# cutoff.net
KiCad netlist of a schematic drawn in EAGLE
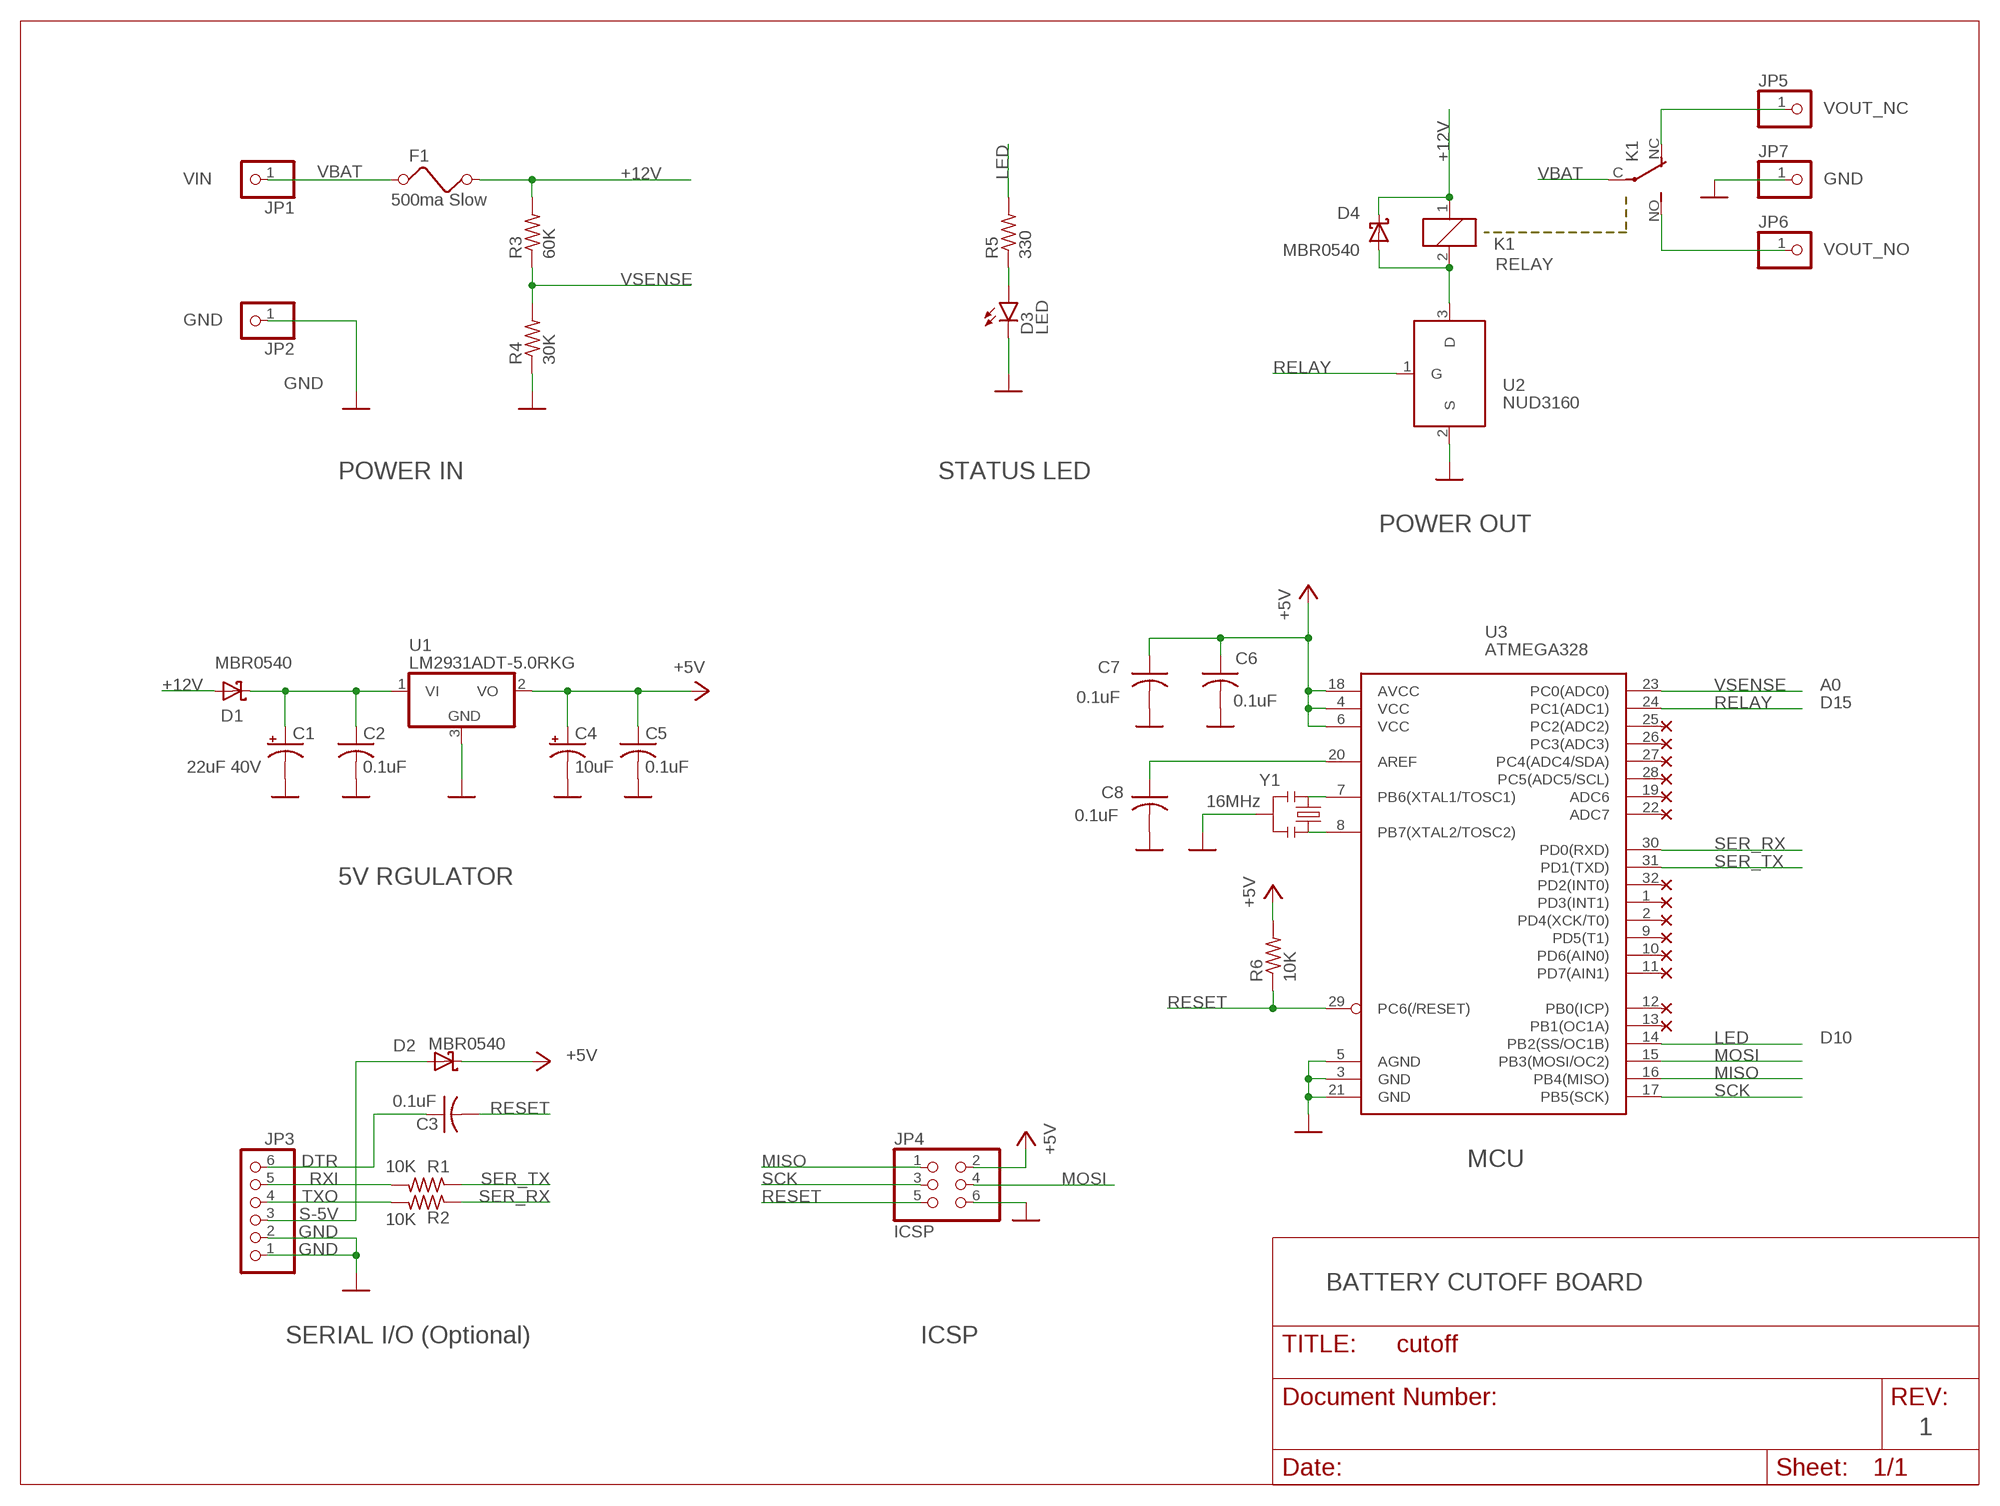
[diagram p0: schematic, sheet 1]

(export (version "E")
  (design (tool "Eeschema 10.0.6"))
  (components
    (comp (ref "C1")
      (value "22uF 40V")
      (footprint "eagle-import:UD-6,3X5,8_NICHICON")
      (libsource (lib "eagle-import") (part "CPOL-USUD-6,3X5,8"))
    )
    (comp (ref "C2")
      (value "0.1uF")
      (footprint "eagle-import:C0603K")
      (libsource (lib "eagle-import") (part "C-USC0603K"))
    )
    (comp (ref "C3")
      (value "0.1uF")
      (footprint "eagle-import:C0603K")
      (libsource (lib "eagle-import") (part "C-USC0603K"))
    )
    (comp (ref "C4")
      (value "10uF")
      (footprint "eagle-import:A_3216-18R")
      (libsource (lib "eagle-import") (part "CPOL-USA/3216-18R"))
    )
    (comp (ref "C5")
      (value "0.1uF")
      (footprint "eagle-import:C0603K")
      (libsource (lib "eagle-import") (part "C-USC0603K"))
    )
    (comp (ref "C6")
      (value "0.1uF")
      (footprint "eagle-import:C0603K")
      (libsource (lib "eagle-import") (part "C-USC0603K"))
    )
    (comp (ref "C7")
      (value "0.1uF")
      (footprint "eagle-import:C0603K")
      (libsource (lib "eagle-import") (part "C-USC0603K"))
    )
    (comp (ref "C8")
      (value "0.1uF")
      (footprint "eagle-import:C0603K")
      (libsource (lib "eagle-import") (part "C-USC0603K"))
    )
    (comp (ref "D1")
      (value "MBR0540")
      (footprint "eagle-import:SOD123FL")
      (libsource (lib "eagle-import") (part "SMF5.0AT1"))
    )
    (comp (ref "D2")
      (value "MBR0540")
      (footprint "eagle-import:SOD123FL")
      (libsource (lib "eagle-import") (part "SMF5.0AT1"))
    )
    (comp (ref "D3")
      (value "LED")
      (footprint "eagle-import:LED")
      (libsource (lib "eagle-import") (part "LED"))
    )
    (comp (ref "D4")
      (value "MBR0540")
      (footprint "eagle-import:SOD123FL")
      (libsource (lib "eagle-import") (part "SMF5.0AT1"))
    )
    (comp (ref "F1")
      (value "500ma Slow")
      (footprint "eagle-import:1206")
      (libsource (lib "eagle-import") (part "FUSE"))
    )
    (comp (ref "JP1")
      (value "WIRE_PAD")
      (footprint "eagle-import:WIRE_PAD")
      (libsource (lib "eagle-import") (part "WIRE_PAD"))
    )
    (comp (ref "JP2")
      (value "WIRE_PAD")
      (footprint "eagle-import:WIRE_PAD")
      (libsource (lib "eagle-import") (part "WIRE_PAD"))
    )
    (comp (ref "JP3")
      (value "PINHD-1X6")
      (footprint "eagle-import:1X06")
      (libsource (lib "eagle-import") (part "PINHD-1X6"))
    )
    (comp (ref "JP4")
      (value "ICSP")
      (footprint "eagle-import:2X03")
      (libsource (lib "eagle-import") (part "PINHD-2X3"))
    )
    (comp (ref "JP5")
      (value "WIRE_PAD")
      (footprint "eagle-import:WIRE_PAD")
      (libsource (lib "eagle-import") (part "WIRE_PAD"))
    )
    (comp (ref "JP6")
      (value "WIRE_PAD")
      (footprint "eagle-import:WIRE_PAD")
      (libsource (lib "eagle-import") (part "WIRE_PAD"))
    )
    (comp (ref "JP7")
      (value "WIRE_PAD")
      (footprint "eagle-import:WIRE_PAD")
      (libsource (lib "eagle-import") (part "WIRE_PAD"))
    )
    (comp (ref "K1")
      (value "RELAY")
      (footprint "eagle-import:RELAY")
      (libsource (lib "eagle-import") (part "RELAY"))
    )
    (comp (ref "R1")
      (value "10K")
      (footprint "eagle-import:R0402")
      (libsource (lib "eagle-import") (part "R-US_R0402"))
    )
    (comp (ref "R2")
      (value "10K")
      (footprint "eagle-import:R0402")
      (libsource (lib "eagle-import") (part "R-US_R0402"))
    )
    (comp (ref "R3")
      (value "60K")
      (footprint "eagle-import:R0402")
      (libsource (lib "eagle-import") (part "R-US_R0402"))
    )
    (comp (ref "R4")
      (value "30K")
      (footprint "eagle-import:R0402")
      (libsource (lib "eagle-import") (part "R-US_R0402"))
    )
    (comp (ref "R5")
      (value "330")
      (footprint "eagle-import:R0402")
      (libsource (lib "eagle-import") (part "R-US_R0402"))
    )
    (comp (ref "R6")
      (value "10K")
      (footprint "eagle-import:R0402")
      (libsource (lib "eagle-import") (part "R-US_R0402"))
    )
    (comp (ref "U1")
      (value "LM2931ADT-5.0RKG")
      (footprint "eagle-import:LDO")
      (libsource (lib "eagle-import") (part "LDODT"))
    )
    (comp (ref "U2")
      (value "NUD3160")
      (footprint "eagle-import:SOT23")
      (libsource (lib "eagle-import") (part "NUD3160"))
    )
    (comp (ref "U3")
      (value "ATMEGA328")
      (footprint "eagle-import:TQFP32-08")
      (libsource (lib "eagle-import") (part "ATMEGA328"))
    )
    (comp (ref "Y1")
      (value "16MHz")
      (footprint "eagle-import:RESONATOR-SMD")
      (libsource (lib "eagle-import") (part "RESONATORSMD"))
    )
  )
  (nets
    (net (code "1") (name "+5V") (class "Default")
      (node (ref "C4") (pin "+") (pinfunction "+_+") (pintype "passive"))
      (node (ref "C5") (pin "1") (pinfunction "1_1") (pintype "passive"))
      (node (ref "C6") (pin "1") (pinfunction "1_1") (pintype "passive"))
      (node (ref "C7") (pin "1") (pinfunction "1_1") (pintype "passive"))
      (node (ref "D2") (pin "C") (pinfunction "C_C") (pintype "passive"))
      (node (ref "JP4") (pin "2") (pinfunction "2_2") (pintype "passive"))
      (node (ref "R6") (pin "2") (pinfunction "2_2") (pintype "passive"))
      (node (ref "U1") (pin "2") (pinfunction "VO_2") (pintype "passive"))
      (node (ref "U3") (pin "18") (pinfunction "AVCC_18") (pintype "power_in"))
      (node (ref "U3") (pin "4") (pinfunction "VCC_4") (pintype "power_in"))
      (node (ref "U3") (pin "6") (pinfunction "VCC_6") (pintype "power_in"))
    )
    (net (code "2") (name "/+12V") (class "Default")
      (node (ref "D1") (pin "A") (pinfunction "A_A") (pintype "passive"))
      (node (ref "D4") (pin "C") (pinfunction "C_C") (pintype "passive"))
      (node (ref "F1") (pin "2") (pinfunction "2_2") (pintype "passive"))
      (node (ref "K1") (pin "1") (pinfunction "1_1") (pintype "passive"))
      (node (ref "R3") (pin "2") (pinfunction "2_2") (pintype "passive"))
    )
    (net (code "3") (name "/DTR") (class "Default")
      (node (ref "C3") (pin "1") (pinfunction "1_1") (pintype "passive"))
      (node (ref "JP3") (pin "6") (pinfunction "6_6") (pintype "passive"))
    )
    (net (code "4") (name "/LED") (class "Default")
      (node (ref "R5") (pin "2") (pinfunction "2_2") (pintype "passive"))
      (node (ref "U3") (pin "14") (pinfunction "PB2(SS/OC1B)_14") (pintype "bidirectional"))
    )
    (net (code "5") (name "/MISO") (class "Default")
      (node (ref "JP4") (pin "1") (pinfunction "1_1") (pintype "passive"))
      (node (ref "U3") (pin "16") (pinfunction "PB4(MISO)_16") (pintype "bidirectional"))
    )
    (net (code "6") (name "/MOSI") (class "Default")
      (node (ref "JP4") (pin "4") (pinfunction "4_4") (pintype "passive"))
      (node (ref "U3") (pin "15") (pinfunction "PB3(MOSI/OC2)_15") (pintype "bidirectional"))
    )
    (net (code "7") (name "/RELAY") (class "Default")
      (node (ref "U2") (pin "1") (pinfunction "G_1") (pintype "passive"))
      (node (ref "U3") (pin "24") (pinfunction "PC1(ADC1)_24") (pintype "bidirectional"))
    )
    (net (code "8") (name "/RESET") (class "Default")
      (node (ref "C3") (pin "2") (pinfunction "2_2") (pintype "passive"))
      (node (ref "JP4") (pin "5") (pinfunction "5_5") (pintype "passive"))
      (node (ref "R6") (pin "1") (pinfunction "1_1") (pintype "passive"))
      (node (ref "U3") (pin "29") (pinfunction "PC6(/RESET)_29") (pintype "bidirectional"))
    )
    (net (code "9") (name "/RXI") (class "Default")
      (node (ref "JP3") (pin "5") (pinfunction "5_5") (pintype "passive"))
      (node (ref "R1") (pin "2") (pinfunction "2_2") (pintype "passive"))
    )
    (net (code "10") (name "/S-5V") (class "Default")
      (node (ref "D2") (pin "A") (pinfunction "A_A") (pintype "passive"))
      (node (ref "JP3") (pin "3") (pinfunction "3_3") (pintype "passive"))
    )
    (net (code "11") (name "/SCK") (class "Default")
      (node (ref "JP4") (pin "3") (pinfunction "3_3") (pintype "passive"))
      (node (ref "U3") (pin "17") (pinfunction "PB5(SCK)_17") (pintype "bidirectional"))
    )
    (net (code "12") (name "/SER_RX") (class "Default")
      (node (ref "R2") (pin "1") (pinfunction "1_1") (pintype "passive"))
      (node (ref "U3") (pin "30") (pinfunction "PD0(RXD)_30") (pintype "bidirectional"))
    )
    (net (code "13") (name "/SER_TX") (class "Default")
      (node (ref "R1") (pin "1") (pinfunction "1_1") (pintype "passive"))
      (node (ref "U3") (pin "31") (pinfunction "PD1(TXD)_31") (pintype "bidirectional"))
    )
    (net (code "14") (name "/TXO") (class "Default")
      (node (ref "JP3") (pin "4") (pinfunction "4_4") (pintype "passive"))
      (node (ref "R2") (pin "2") (pinfunction "2_2") (pintype "passive"))
    )
    (net (code "15") (name "/VBAT") (class "Default")
      (node (ref "F1") (pin "1") (pinfunction "1_1") (pintype "passive"))
      (node (ref "JP1") (pin "1") (pinfunction "1_1") (pintype "passive"))
      (node (ref "K1") (pin "C") (pinfunction "P_C") (pintype "passive"))
    )
    (net (code "16") (name "/VSENSE") (class "Default")
      (node (ref "R3") (pin "1") (pinfunction "1_1") (pintype "passive"))
      (node (ref "R4") (pin "2") (pinfunction "2_2") (pintype "passive"))
      (node (ref "U3") (pin "23") (pinfunction "PC0(ADC0)_23") (pintype "bidirectional"))
    )
    (net (code "17") (name "GND") (class "Default")
      (node (ref "C1") (pin "-") (pinfunction "-_-") (pintype "passive"))
      (node (ref "C2") (pin "2") (pinfunction "2_2") (pintype "passive"))
      (node (ref "C4") (pin "-") (pinfunction "-_-") (pintype "passive"))
      (node (ref "C5") (pin "2") (pinfunction "2_2") (pintype "passive"))
      (node (ref "C6") (pin "2") (pinfunction "2_2") (pintype "passive"))
      (node (ref "C7") (pin "2") (pinfunction "2_2") (pintype "passive"))
      (node (ref "C8") (pin "2") (pinfunction "2_2") (pintype "passive"))
      (node (ref "D3") (pin "K") (pinfunction "C_K") (pintype "passive"))
      (node (ref "JP2") (pin "1") (pinfunction "1_1") (pintype "passive"))
      (node (ref "JP3") (pin "1") (pinfunction "1_1") (pintype "passive"))
      (node (ref "JP3") (pin "2") (pinfunction "2_2") (pintype "passive"))
      (node (ref "JP4") (pin "6") (pinfunction "6_6") (pintype "passive"))
      (node (ref "JP7") (pin "1") (pinfunction "1_1") (pintype "passive"))
      (node (ref "R4") (pin "1") (pinfunction "1_1") (pintype "passive"))
      (node (ref "U1") (pin "3") (pinfunction "GND_3") (pintype "passive"))
      (node (ref "U2") (pin "2") (pinfunction "S_2") (pintype "passive"))
      (node (ref "U3") (pin "21") (pinfunction "GND_21") (pintype "power_in"))
      (node (ref "U3") (pin "3") (pinfunction "GND_3") (pintype "power_in"))
      (node (ref "U3") (pin "5") (pinfunction "AGND_5") (pintype "power_in"))
      (node (ref "Y1") (pin "2") (pinfunction "2_2") (pintype "passive"))
    )
    (net (code "18") (name "Net-(D3-PadA)") (class "Default")
      (node (ref "D3") (pin "A") (pinfunction "A_A") (pintype "passive"))
      (node (ref "R5") (pin "1") (pinfunction "1_1") (pintype "passive"))
    )
    (net (code "19") (name "Net-(K1B-O)") (class "Default")
      (node (ref "JP5") (pin "1") (pinfunction "1_1") (pintype "passive"))
      (node (ref "K1") (pin "NC") (pinfunction "O_NC") (pintype "passive"))
    )
    (net (code "20") (name "Net-(K1B-S)") (class "Default")
      (node (ref "JP6") (pin "1") (pinfunction "1_1") (pintype "passive"))
      (node (ref "K1") (pin "NO") (pinfunction "S_NO") (pintype "passive"))
    )
    (net (code "21") (name "Net-(U1-VI)") (class "Default")
      (node (ref "C1") (pin "+") (pinfunction "+_+") (pintype "passive"))
      (node (ref "C2") (pin "1") (pinfunction "1_1") (pintype "passive"))
      (node (ref "D1") (pin "C") (pinfunction "C_C") (pintype "passive"))
      (node (ref "U1") (pin "1") (pinfunction "VI_1") (pintype "input"))
    )
    (net (code "22") (name "Net-(U2-D)") (class "Default")
      (node (ref "D4") (pin "A") (pinfunction "A_A") (pintype "passive"))
      (node (ref "K1") (pin "2") (pinfunction "2_2") (pintype "passive"))
      (node (ref "U2") (pin "3") (pinfunction "D_3") (pintype "passive"))
    )
    (net (code "23") (name "Net-(U3-AREF)") (class "Default")
      (node (ref "C8") (pin "1") (pinfunction "1_1") (pintype "passive"))
      (node (ref "U3") (pin "20") (pinfunction "AREF_20") (pintype "power_in"))
    )
    (net (code "24") (name "Net-(U3-PB6(XTAL1{slash}TOSC1))") (class "Default")
      (node (ref "U3") (pin "7") (pinfunction "PB6(XTAL1/TOSC1)_7") (pintype "bidirectional"))
      (node (ref "Y1") (pin "3") (pinfunction "3_3") (pintype "passive"))
    )
    (net (code "25") (name "Net-(U3-PB7(XTAL2{slash}TOSC2))") (class "Default")
      (node (ref "U3") (pin "8") (pinfunction "PB7(XTAL2/TOSC2)_8") (pintype "bidirectional"))
      (node (ref "Y1") (pin "1") (pinfunction "1_1") (pintype "passive"))
    )
    (net (code "26") (name "unconnected-(U3-ADC6-Pad19)") (class "Default")
      (node (ref "U3") (pin "19") (pinfunction "ADC6_19") (pintype "bidirectional"))
    )
    (net (code "27") (name "unconnected-(U3-ADC7-Pad22)") (class "Default")
      (node (ref "U3") (pin "22") (pinfunction "ADC7_22") (pintype "bidirectional"))
    )
    (net (code "28") (name "unconnected-(U3-PB0(ICP)-Pad12)") (class "Default")
      (node (ref "U3") (pin "12") (pinfunction "PB0(ICP)_12") (pintype "bidirectional"))
    )
    (net (code "29") (name "unconnected-(U3-PB1(OC1A)-Pad13)") (class "Default")
      (node (ref "U3") (pin "13") (pinfunction "PB1(OC1A)_13") (pintype "bidirectional"))
    )
    (net (code "30") (name "unconnected-(U3-PC2(ADC2)-Pad25)") (class "Default")
      (node (ref "U3") (pin "25") (pinfunction "PC2(ADC2)_25") (pintype "bidirectional"))
    )
    (net (code "31") (name "unconnected-(U3-PC3(ADC3)-Pad26)") (class "Default")
      (node (ref "U3") (pin "26") (pinfunction "PC3(ADC3)_26") (pintype "bidirectional"))
    )
    (net (code "32") (name "unconnected-(U3-PC4(ADC4{slash}SDA)-Pad27)") (class "Default")
      (node (ref "U3") (pin "27") (pinfunction "PC4(ADC4/SDA)_27") (pintype "bidirectional"))
    )
    (net (code "33") (name "unconnected-(U3-PC5(ADC5{slash}SCL)-Pad28)") (class "Default")
      (node (ref "U3") (pin "28") (pinfunction "PC5(ADC5/SCL)_28") (pintype "bidirectional"))
    )
    (net (code "34") (name "unconnected-(U3-PD2(INT0)-Pad32)") (class "Default")
      (node (ref "U3") (pin "32") (pinfunction "PD2(INT0)_32") (pintype "bidirectional"))
    )
    (net (code "35") (name "unconnected-(U3-PD3(INT1)-Pad1)") (class "Default")
      (node (ref "U3") (pin "1") (pinfunction "PD3(INT1)_1") (pintype "bidirectional"))
    )
    (net (code "36") (name "unconnected-(U3-PD4(XCK{slash}T0)-Pad2)") (class "Default")
      (node (ref "U3") (pin "2") (pinfunction "PD4(XCK/T0)_2") (pintype "bidirectional"))
    )
    (net (code "37") (name "unconnected-(U3-PD5(T1)-Pad9)") (class "Default")
      (node (ref "U3") (pin "9") (pinfunction "PD5(T1)_9") (pintype "bidirectional"))
    )
    (net (code "38") (name "unconnected-(U3-PD6(AIN0)-Pad10)") (class "Default")
      (node (ref "U3") (pin "10") (pinfunction "PD6(AIN0)_10") (pintype "bidirectional"))
    )
    (net (code "39") (name "unconnected-(U3-PD7(AIN1)-Pad11)") (class "Default")
      (node (ref "U3") (pin "11") (pinfunction "PD7(AIN1)_11") (pintype "bidirectional"))
    )
  )
)
